# HallSensor.net
KiCad netlist of a schematic drawn in EAGLE
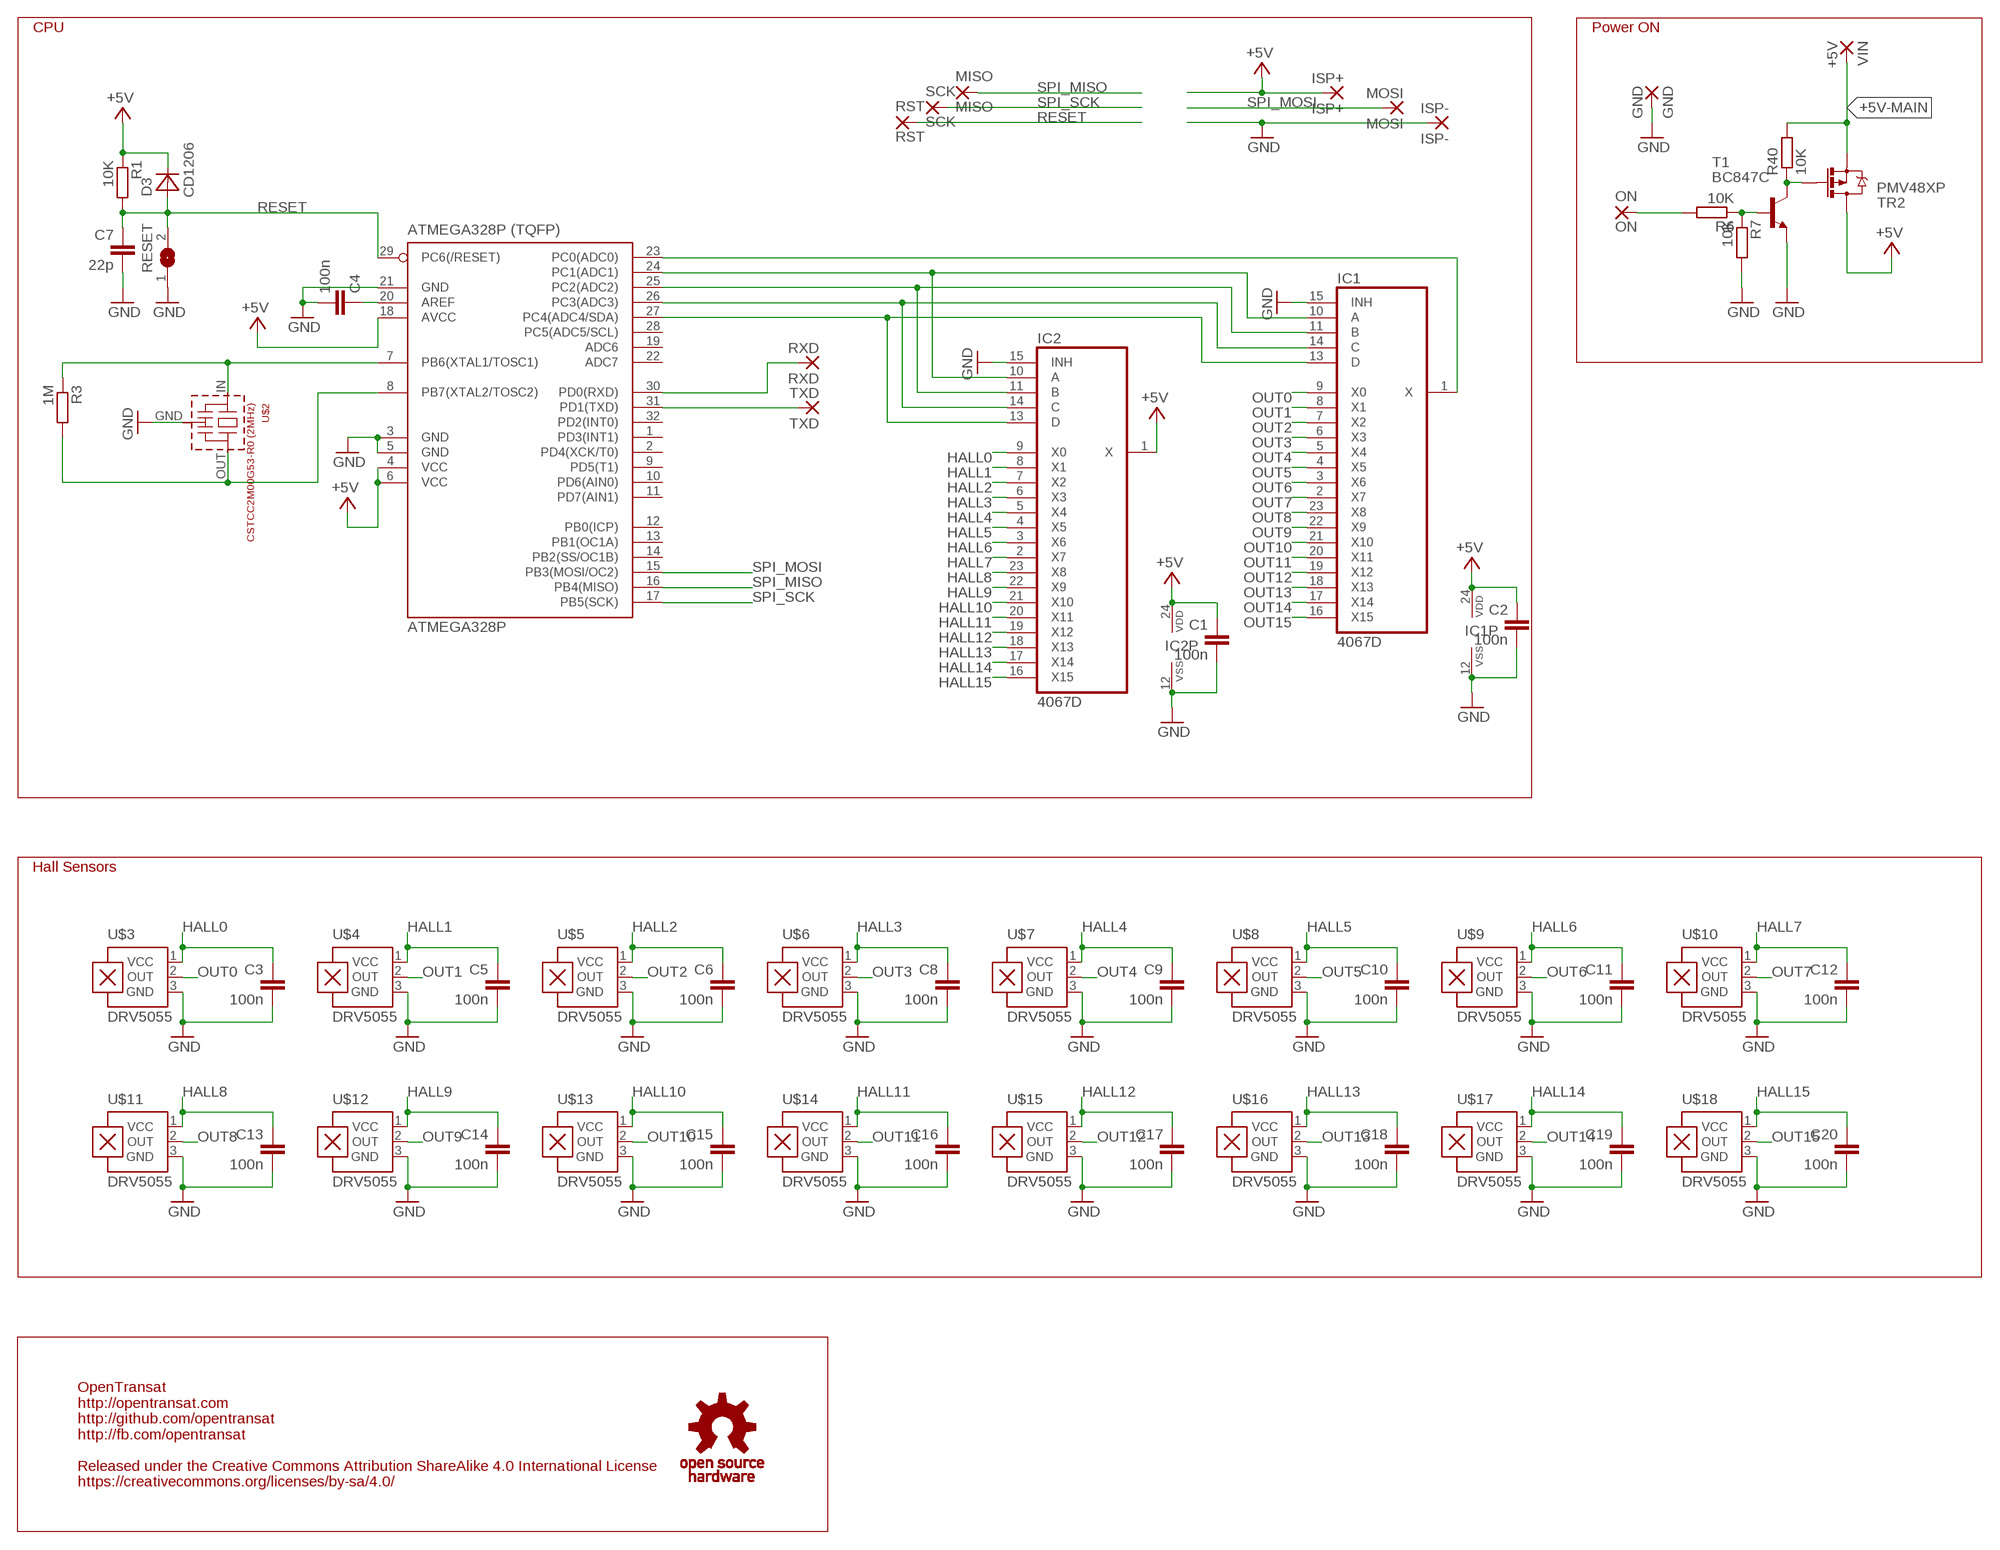
[diagram p0: schematic, sheet 1]

(export (version "E")
  (design (tool "Eeschema 10.0.6"))
  (components
    (comp (ref "ATMEGA328P")
      (value "ATMEGA328P (TQFP)")
      (footprint "eagle-import:TQFP32-08")
      (fields (field (name "MPN") "ATMEGA8-16AU"))
      (libsource (lib "eagle-import") (part "MEGA8-AI"))
    )
    (comp (ref "C1")
      (value "100n")
      (footprint "eagle-import:C0603")
      (libsource (lib "eagle-import") (part "C-EUC0603"))
    )
    (comp (ref "C2")
      (value "100n")
      (footprint "eagle-import:C0603")
      (libsource (lib "eagle-import") (part "C-EUC0603"))
    )
    (comp (ref "C3")
      (value "100n")
      (footprint "eagle-import:C0603")
      (libsource (lib "eagle-import") (part "C-EUC0603"))
    )
    (comp (ref "C4")
      (value "100n")
      (footprint "eagle-import:C0603")
      (libsource (lib "eagle-import") (part "C-EUC0603"))
    )
    (comp (ref "C5")
      (value "100n")
      (footprint "eagle-import:C0603")
      (libsource (lib "eagle-import") (part "C-EUC0603"))
    )
    (comp (ref "C6")
      (value "100n")
      (footprint "eagle-import:C0603")
      (libsource (lib "eagle-import") (part "C-EUC0603"))
    )
    (comp (ref "C7")
      (value "22p")
      (footprint "eagle-import:C0603")
      (libsource (lib "eagle-import") (part "C-EUC0603"))
    )
    (comp (ref "C8")
      (value "100n")
      (footprint "eagle-import:C0603")
      (libsource (lib "eagle-import") (part "C-EUC0603"))
    )
    (comp (ref "C9")
      (value "100n")
      (footprint "eagle-import:C0603")
      (libsource (lib "eagle-import") (part "C-EUC0603"))
    )
    (comp (ref "C10")
      (value "100n")
      (footprint "eagle-import:C0603")
      (libsource (lib "eagle-import") (part "C-EUC0603"))
    )
    (comp (ref "C11")
      (value "100n")
      (footprint "eagle-import:C0603")
      (libsource (lib "eagle-import") (part "C-EUC0603"))
    )
    (comp (ref "C12")
      (value "100n")
      (footprint "eagle-import:C0603")
      (libsource (lib "eagle-import") (part "C-EUC0603"))
    )
    (comp (ref "C13")
      (value "100n")
      (footprint "eagle-import:C0603")
      (libsource (lib "eagle-import") (part "C-EUC0603"))
    )
    (comp (ref "C14")
      (value "100n")
      (footprint "eagle-import:C0603")
      (libsource (lib "eagle-import") (part "C-EUC0603"))
    )
    (comp (ref "C15")
      (value "100n")
      (footprint "eagle-import:C0603")
      (libsource (lib "eagle-import") (part "C-EUC0603"))
    )
    (comp (ref "C16")
      (value "100n")
      (footprint "eagle-import:C0603")
      (libsource (lib "eagle-import") (part "C-EUC0603"))
    )
    (comp (ref "C17")
      (value "100n")
      (footprint "eagle-import:C0603")
      (libsource (lib "eagle-import") (part "C-EUC0603"))
    )
    (comp (ref "C18")
      (value "100n")
      (footprint "eagle-import:C0603")
      (libsource (lib "eagle-import") (part "C-EUC0603"))
    )
    (comp (ref "C19")
      (value "100n")
      (footprint "eagle-import:C0603")
      (libsource (lib "eagle-import") (part "C-EUC0603"))
    )
    (comp (ref "C20")
      (value "100n")
      (footprint "eagle-import:C0603")
      (libsource (lib "eagle-import") (part "C-EUC0603"))
    )
    (comp (ref "D3")
      (value "CD1206")
      (footprint "eagle-import:R1206")
      (libsource (lib "eagle-import") (part "CD1206"))
    )
    (comp (ref "GND")
      (value "GND")
      (footprint "eagle-import:SMD2,54-5,08")
      (libsource (lib "eagle-import") (part "SMD5"))
    )
    (comp (ref "IC1")
      (value "4067D")
      (footprint "eagle-import:SO24W")
      (libsource (lib "eagle-import") (part "4067D"))
    )
    (comp (ref "IC2")
      (value "4067D")
      (footprint "eagle-import:SO24W")
      (libsource (lib "eagle-import") (part "4067D"))
    )
    (comp (ref "ISP+")
      (value "ISP+")
      (footprint "eagle-import:SMD2,54-5,08")
      (libsource (lib "eagle-import") (part "SMD5"))
    )
    (comp (ref "ISP-")
      (value "ISP-")
      (footprint "eagle-import:SMD2,54-5,08")
      (libsource (lib "eagle-import") (part "SMD5"))
    )
    (comp (ref "MISO")
      (value "MISO")
      (footprint "eagle-import:SMD2,54-5,08")
      (libsource (lib "eagle-import") (part "SMD5"))
    )
    (comp (ref "MOSI")
      (value "MOSI")
      (footprint "eagle-import:SMD2,54-5,08")
      (libsource (lib "eagle-import") (part "SMD5"))
    )
    (comp (ref "ON")
      (value "ON")
      (footprint "eagle-import:SMD2,54-5,08")
      (libsource (lib "eagle-import") (part "SMD5"))
    )
    (comp (ref "R1")
      (value "10K")
      (footprint "eagle-import:R0603")
      (libsource (lib "eagle-import") (part "R-EU_R0603"))
    )
    (comp (ref "R3")
      (value "1M")
      (footprint "eagle-import:R0603")
      (libsource (lib "eagle-import") (part "R-EU_R0603"))
    )
    (comp (ref "R6")
      (value "10K")
      (footprint "eagle-import:R0603")
      (libsource (lib "eagle-import") (part "R-EU_R0603"))
    )
    (comp (ref "R7")
      (value "10K")
      (footprint "eagle-import:R0603")
      (libsource (lib "eagle-import") (part "R-EU_R0603"))
    )
    (comp (ref "R40")
      (value "10K")
      (footprint "eagle-import:R0603")
      (libsource (lib "eagle-import") (part "R-EU_R0603"))
    )
    (comp (ref "RESET")
      (value "SJW")
      (footprint "eagle-import:SJW")
      (libsource (lib "eagle-import") (part "SJW"))
    )
    (comp (ref "RST")
      (value "RST")
      (footprint "eagle-import:SMD2,54-5,08")
      (libsource (lib "eagle-import") (part "SMD5"))
    )
    (comp (ref "RXD")
      (value "RXD")
      (footprint "eagle-import:SMD2,54-5,08")
      (libsource (lib "eagle-import") (part "SMD5"))
    )
    (comp (ref "SCK")
      (value "SCK")
      (footprint "eagle-import:SMD2,54-5,08")
      (libsource (lib "eagle-import") (part "SMD5"))
    )
    (comp (ref "T1")
      (value "BC847C")
      (footprint "eagle-import:SOT23")
      (libsource (lib "eagle-import") (part "BC847"))
    )
    (comp (ref "TR2")
      (value "PMV48XP")
      (footprint "eagle-import:SOT23-3")
      (libsource (lib "eagle-import") (part "MOSFET-PCHANNEL_SOT23-3"))
    )
    (comp (ref "TXD")
      (value "TXD")
      (footprint "eagle-import:SMD2,54-5,08")
      (libsource (lib "eagle-import") (part "SMD5"))
    )
    (comp (ref "U$1")
      (value "OSHW_S")
      (footprint "eagle-import:OSHWS")
      (libsource (lib "eagle-import") (part "OSHW_S"))
    )
    (comp (ref "U$2")
      (value "CSTCC2M00G53-R0 (2MHz)")
      (footprint "eagle-import:CSTCC")
      (libsource (lib "eagle-import") (part "CSTCC"))
    )
    (comp (ref "U$3")
      (value "DRV5055")
      (footprint "eagle-import:SOT23")
      (libsource (lib "eagle-import") (part "DRV5055"))
    )
    (comp (ref "U$4")
      (value "DRV5055")
      (footprint "eagle-import:SOT23")
      (libsource (lib "eagle-import") (part "DRV5055"))
    )
    (comp (ref "U$5")
      (value "DRV5055")
      (footprint "eagle-import:SOT23")
      (libsource (lib "eagle-import") (part "DRV5055"))
    )
    (comp (ref "U$6")
      (value "DRV5055")
      (footprint "eagle-import:SOT23")
      (libsource (lib "eagle-import") (part "DRV5055"))
    )
    (comp (ref "U$7")
      (value "DRV5055")
      (footprint "eagle-import:SOT23")
      (libsource (lib "eagle-import") (part "DRV5055"))
    )
    (comp (ref "U$8")
      (value "DRV5055")
      (footprint "eagle-import:SOT23")
      (libsource (lib "eagle-import") (part "DRV5055"))
    )
    (comp (ref "U$9")
      (value "DRV5055")
      (footprint "eagle-import:SOT23")
      (libsource (lib "eagle-import") (part "DRV5055"))
    )
    (comp (ref "U$10")
      (value "DRV5055")
      (footprint "eagle-import:SOT23")
      (libsource (lib "eagle-import") (part "DRV5055"))
    )
    (comp (ref "U$11")
      (value "DRV5055")
      (footprint "eagle-import:SOT23")
      (libsource (lib "eagle-import") (part "DRV5055"))
    )
    (comp (ref "U$12")
      (value "DRV5055")
      (footprint "eagle-import:SOT23")
      (libsource (lib "eagle-import") (part "DRV5055"))
    )
    (comp (ref "U$13")
      (value "DRV5055")
      (footprint "eagle-import:SOT23")
      (libsource (lib "eagle-import") (part "DRV5055"))
    )
    (comp (ref "U$14")
      (value "DRV5055")
      (footprint "eagle-import:SOT23")
      (libsource (lib "eagle-import") (part "DRV5055"))
    )
    (comp (ref "U$15")
      (value "DRV5055")
      (footprint "eagle-import:SOT23")
      (libsource (lib "eagle-import") (part "DRV5055"))
    )
    (comp (ref "U$16")
      (value "DRV5055")
      (footprint "eagle-import:SOT23")
      (libsource (lib "eagle-import") (part "DRV5055"))
    )
    (comp (ref "U$17")
      (value "DRV5055")
      (footprint "eagle-import:SOT23")
      (libsource (lib "eagle-import") (part "DRV5055"))
    )
    (comp (ref "U$18")
      (value "DRV5055")
      (footprint "eagle-import:SOT23")
      (libsource (lib "eagle-import") (part "DRV5055"))
    )
    (comp (ref "VIN")
      (value "+5V")
      (footprint "eagle-import:SMD2,54-5,08")
      (libsource (lib "eagle-import") (part "SMD5"))
    )
  )
  (nets
    (net (code "1") (name "+5V") (class "Default")
      (node (ref "ATMEGA328P") (pin "18") (pinfunction "AVCC_18") (pintype "power_in"))
      (node (ref "ATMEGA328P") (pin "4") (pinfunction "VCC_4") (pintype "power_in"))
      (node (ref "ATMEGA328P") (pin "6") (pinfunction "VCC_6") (pintype "power_in"))
      (node (ref "C1") (pin "1") (pinfunction "1_1") (pintype "passive"))
      (node (ref "C2") (pin "1") (pinfunction "1_1") (pintype "passive"))
      (node (ref "D3") (pin "2") (pinfunction "C_2") (pintype "passive"))
      (node (ref "IC1") (pin "24") (pinfunction "VDD_24") (pintype "power_in"))
      (node (ref "IC2") (pin "1") (pinfunction "X_1") (pintype "output"))
      (node (ref "IC2") (pin "24") (pinfunction "VDD_24") (pintype "power_in"))
      (node (ref "ISP+") (pin "1") (pinfunction "P_1") (pintype "passive"))
      (node (ref "R1") (pin "1") (pinfunction "1_1") (pintype "passive"))
      (node (ref "TR2") (pin "3") (pinfunction "D_3") (pintype "passive"))
    )
    (net (code "2") (name "+5V-MAIN") (class "Default")
      (node (ref "R40") (pin "2") (pinfunction "2_2") (pintype "passive"))
      (node (ref "TR2") (pin "2") (pinfunction "S_2") (pintype "passive"))
      (node (ref "VIN") (pin "1") (pinfunction "P_1") (pintype "passive"))
    )
    (net (code "3") (name "/HALL0") (class "Default")
      (node (ref "C3") (pin "1") (pinfunction "1_1") (pintype "passive"))
      (node (ref "IC2") (pin "9") (pinfunction "X0_9") (pintype "input"))
      (node (ref "U$3") (pin "1") (pinfunction "VCC_1") (pintype "power_in"))
    )
    (net (code "4") (name "/HALL1") (class "Default")
      (node (ref "C5") (pin "1") (pinfunction "1_1") (pintype "passive"))
      (node (ref "IC2") (pin "8") (pinfunction "X1_8") (pintype "input"))
      (node (ref "U$4") (pin "1") (pinfunction "VCC_1") (pintype "power_in"))
    )
    (net (code "5") (name "/HALL2") (class "Default")
      (node (ref "C6") (pin "1") (pinfunction "1_1") (pintype "passive"))
      (node (ref "IC2") (pin "7") (pinfunction "X2_7") (pintype "input"))
      (node (ref "U$5") (pin "1") (pinfunction "VCC_1") (pintype "power_in"))
    )
    (net (code "6") (name "/HALL3") (class "Default")
      (node (ref "C8") (pin "1") (pinfunction "1_1") (pintype "passive"))
      (node (ref "IC2") (pin "6") (pinfunction "X3_6") (pintype "input"))
      (node (ref "U$6") (pin "1") (pinfunction "VCC_1") (pintype "power_in"))
    )
    (net (code "7") (name "/HALL4") (class "Default")
      (node (ref "C9") (pin "1") (pinfunction "1_1") (pintype "passive"))
      (node (ref "IC2") (pin "5") (pinfunction "X4_5") (pintype "input"))
      (node (ref "U$7") (pin "1") (pinfunction "VCC_1") (pintype "power_in"))
    )
    (net (code "8") (name "/HALL5") (class "Default")
      (node (ref "C10") (pin "1") (pinfunction "1_1") (pintype "passive"))
      (node (ref "IC2") (pin "4") (pinfunction "X5_4") (pintype "input"))
      (node (ref "U$8") (pin "1") (pinfunction "VCC_1") (pintype "power_in"))
    )
    (net (code "9") (name "/HALL6") (class "Default")
      (node (ref "C11") (pin "1") (pinfunction "1_1") (pintype "passive"))
      (node (ref "IC2") (pin "3") (pinfunction "X6_3") (pintype "input"))
      (node (ref "U$9") (pin "1") (pinfunction "VCC_1") (pintype "power_in"))
    )
    (net (code "10") (name "/HALL7") (class "Default")
      (node (ref "C12") (pin "1") (pinfunction "1_1") (pintype "passive"))
      (node (ref "IC2") (pin "2") (pinfunction "X7_2") (pintype "input"))
      (node (ref "U$10") (pin "1") (pinfunction "VCC_1") (pintype "power_in"))
    )
    (net (code "11") (name "/HALL8") (class "Default")
      (node (ref "C13") (pin "1") (pinfunction "1_1") (pintype "passive"))
      (node (ref "IC2") (pin "23") (pinfunction "X8_23") (pintype "input"))
      (node (ref "U$11") (pin "1") (pinfunction "VCC_1") (pintype "power_in"))
    )
    (net (code "12") (name "/HALL9") (class "Default")
      (node (ref "C14") (pin "1") (pinfunction "1_1") (pintype "passive"))
      (node (ref "IC2") (pin "22") (pinfunction "X9_22") (pintype "input"))
      (node (ref "U$12") (pin "1") (pinfunction "VCC_1") (pintype "power_in"))
    )
    (net (code "13") (name "/HALL10") (class "Default")
      (node (ref "C15") (pin "1") (pinfunction "1_1") (pintype "passive"))
      (node (ref "IC2") (pin "21") (pinfunction "X10_21") (pintype "input"))
      (node (ref "U$13") (pin "1") (pinfunction "VCC_1") (pintype "power_in"))
    )
    (net (code "14") (name "/HALL11") (class "Default")
      (node (ref "C16") (pin "1") (pinfunction "1_1") (pintype "passive"))
      (node (ref "IC2") (pin "20") (pinfunction "X11_20") (pintype "input"))
      (node (ref "U$14") (pin "1") (pinfunction "VCC_1") (pintype "power_in"))
    )
    (net (code "15") (name "/HALL12") (class "Default")
      (node (ref "C17") (pin "1") (pinfunction "1_1") (pintype "passive"))
      (node (ref "IC2") (pin "19") (pinfunction "X12_19") (pintype "input"))
      (node (ref "U$15") (pin "1") (pinfunction "VCC_1") (pintype "power_in"))
    )
    (net (code "16") (name "/HALL13") (class "Default")
      (node (ref "C18") (pin "1") (pinfunction "1_1") (pintype "passive"))
      (node (ref "IC2") (pin "18") (pinfunction "X13_18") (pintype "input"))
      (node (ref "U$16") (pin "1") (pinfunction "VCC_1") (pintype "power_in"))
    )
    (net (code "17") (name "/HALL14") (class "Default")
      (node (ref "C19") (pin "1") (pinfunction "1_1") (pintype "passive"))
      (node (ref "IC2") (pin "17") (pinfunction "X14_17") (pintype "input"))
      (node (ref "U$17") (pin "1") (pinfunction "VCC_1") (pintype "power_in"))
    )
    (net (code "18") (name "/HALL15") (class "Default")
      (node (ref "C20") (pin "1") (pinfunction "1_1") (pintype "passive"))
      (node (ref "IC2") (pin "16") (pinfunction "X15_16") (pintype "input"))
      (node (ref "U$18") (pin "1") (pinfunction "VCC_1") (pintype "power_in"))
    )
    (net (code "19") (name "/OUT0") (class "Default")
      (node (ref "IC1") (pin "9") (pinfunction "X0_9") (pintype "input"))
      (node (ref "U$3") (pin "2") (pinfunction "OUT_2") (pintype "output"))
    )
    (net (code "20") (name "/OUT1") (class "Default")
      (node (ref "IC1") (pin "8") (pinfunction "X1_8") (pintype "input"))
      (node (ref "U$4") (pin "2") (pinfunction "OUT_2") (pintype "output"))
    )
    (net (code "21") (name "/OUT2") (class "Default")
      (node (ref "IC1") (pin "7") (pinfunction "X2_7") (pintype "input"))
      (node (ref "U$5") (pin "2") (pinfunction "OUT_2") (pintype "output"))
    )
    (net (code "22") (name "/OUT3") (class "Default")
      (node (ref "IC1") (pin "6") (pinfunction "X3_6") (pintype "input"))
      (node (ref "U$6") (pin "2") (pinfunction "OUT_2") (pintype "output"))
    )
    (net (code "23") (name "/OUT4") (class "Default")
      (node (ref "IC1") (pin "5") (pinfunction "X4_5") (pintype "input"))
      (node (ref "U$7") (pin "2") (pinfunction "OUT_2") (pintype "output"))
    )
    (net (code "24") (name "/OUT5") (class "Default")
      (node (ref "IC1") (pin "4") (pinfunction "X5_4") (pintype "input"))
      (node (ref "U$8") (pin "2") (pinfunction "OUT_2") (pintype "output"))
    )
    (net (code "25") (name "/OUT6") (class "Default")
      (node (ref "IC1") (pin "3") (pinfunction "X6_3") (pintype "input"))
      (node (ref "U$9") (pin "2") (pinfunction "OUT_2") (pintype "output"))
    )
    (net (code "26") (name "/OUT7") (class "Default")
      (node (ref "IC1") (pin "2") (pinfunction "X7_2") (pintype "input"))
      (node (ref "U$10") (pin "2") (pinfunction "OUT_2") (pintype "output"))
    )
    (net (code "27") (name "/OUT8") (class "Default")
      (node (ref "IC1") (pin "23") (pinfunction "X8_23") (pintype "input"))
      (node (ref "U$11") (pin "2") (pinfunction "OUT_2") (pintype "output"))
    )
    (net (code "28") (name "/OUT9") (class "Default")
      (node (ref "IC1") (pin "22") (pinfunction "X9_22") (pintype "input"))
      (node (ref "U$12") (pin "2") (pinfunction "OUT_2") (pintype "output"))
    )
    (net (code "29") (name "/OUT10") (class "Default")
      (node (ref "IC1") (pin "21") (pinfunction "X10_21") (pintype "input"))
      (node (ref "U$13") (pin "2") (pinfunction "OUT_2") (pintype "output"))
    )
    (net (code "30") (name "/OUT11") (class "Default")
      (node (ref "IC1") (pin "20") (pinfunction "X11_20") (pintype "input"))
      (node (ref "U$14") (pin "2") (pinfunction "OUT_2") (pintype "output"))
    )
    (net (code "31") (name "/OUT12") (class "Default")
      (node (ref "IC1") (pin "19") (pinfunction "X12_19") (pintype "input"))
      (node (ref "U$15") (pin "2") (pinfunction "OUT_2") (pintype "output"))
    )
    (net (code "32") (name "/OUT13") (class "Default")
      (node (ref "IC1") (pin "18") (pinfunction "X13_18") (pintype "input"))
      (node (ref "U$16") (pin "2") (pinfunction "OUT_2") (pintype "output"))
    )
    (net (code "33") (name "/OUT14") (class "Default")
      (node (ref "IC1") (pin "17") (pinfunction "X14_17") (pintype "input"))
      (node (ref "U$17") (pin "2") (pinfunction "OUT_2") (pintype "output"))
    )
    (net (code "34") (name "/OUT15") (class "Default")
      (node (ref "IC1") (pin "16") (pinfunction "X15_16") (pintype "input"))
      (node (ref "U$18") (pin "2") (pinfunction "OUT_2") (pintype "output"))
    )
    (net (code "35") (name "/RESET") (class "Default")
      (node (ref "ATMEGA328P") (pin "29") (pinfunction "PC6(/RESET)_29") (pintype "bidirectional"))
      (node (ref "C7") (pin "1") (pinfunction "1_1") (pintype "passive"))
      (node (ref "D3") (pin "1") (pinfunction "A_1") (pintype "passive"))
      (node (ref "R1") (pin "2") (pinfunction "2_2") (pintype "passive"))
      (node (ref "RESET") (pin "2") (pinfunction "2_2") (pintype "passive"))
      (node (ref "RST") (pin "1") (pinfunction "P_1") (pintype "passive"))
    )
    (net (code "36") (name "/SPI_MISO") (class "Default")
      (node (ref "ATMEGA328P") (pin "16") (pinfunction "PB4(MISO)_16") (pintype "bidirectional"))
      (node (ref "MISO") (pin "1") (pinfunction "P_1") (pintype "passive"))
    )
    (net (code "37") (name "/SPI_MOSI") (class "Default")
      (node (ref "ATMEGA328P") (pin "15") (pinfunction "PB3(MOSI/OC2)_15") (pintype "bidirectional"))
      (node (ref "MOSI") (pin "1") (pinfunction "P_1") (pintype "passive"))
    )
    (net (code "38") (name "/SPI_SCK") (class "Default")
      (node (ref "ATMEGA328P") (pin "17") (pinfunction "PB5(SCK)_17") (pintype "bidirectional"))
      (node (ref "SCK") (pin "1") (pinfunction "P_1") (pintype "passive"))
    )
    (net (code "39") (name "GND") (class "Default")
      (node (ref "ATMEGA328P") (pin "21") (pinfunction "GND_21") (pintype "power_in"))
      (node (ref "ATMEGA328P") (pin "3") (pinfunction "GND_3") (pintype "power_in"))
      (node (ref "ATMEGA328P") (pin "5") (pinfunction "GND_5") (pintype "power_in"))
      (node (ref "C1") (pin "2") (pinfunction "2_2") (pintype "passive"))
      (node (ref "C10") (pin "2") (pinfunction "2_2") (pintype "passive"))
      (node (ref "C11") (pin "2") (pinfunction "2_2") (pintype "passive"))
      (node (ref "C12") (pin "2") (pinfunction "2_2") (pintype "passive"))
      (node (ref "C13") (pin "2") (pinfunction "2_2") (pintype "passive"))
      (node (ref "C14") (pin "2") (pinfunction "2_2") (pintype "passive"))
      (node (ref "C15") (pin "2") (pinfunction "2_2") (pintype "passive"))
      (node (ref "C16") (pin "2") (pinfunction "2_2") (pintype "passive"))
      (node (ref "C17") (pin "2") (pinfunction "2_2") (pintype "passive"))
      (node (ref "C18") (pin "2") (pinfunction "2_2") (pintype "passive"))
      (node (ref "C19") (pin "2") (pinfunction "2_2") (pintype "passive"))
      (node (ref "C2") (pin "2") (pinfunction "2_2") (pintype "passive"))
      (node (ref "C20") (pin "2") (pinfunction "2_2") (pintype "passive"))
      (node (ref "C3") (pin "2") (pinfunction "2_2") (pintype "passive"))
      (node (ref "C4") (pin "2") (pinfunction "2_2") (pintype "passive"))
      (node (ref "C5") (pin "2") (pinfunction "2_2") (pintype "passive"))
      (node (ref "C6") (pin "2") (pinfunction "2_2") (pintype "passive"))
      (node (ref "C7") (pin "2") (pinfunction "2_2") (pintype "passive"))
      (node (ref "C8") (pin "2") (pinfunction "2_2") (pintype "passive"))
      (node (ref "C9") (pin "2") (pinfunction "2_2") (pintype "passive"))
      (node (ref "GND") (pin "1") (pinfunction "P_1") (pintype "passive"))
      (node (ref "IC1") (pin "12") (pinfunction "VSS_12") (pintype "power_in"))
      (node (ref "IC1") (pin "15") (pinfunction "INH_15") (pintype "input"))
      (node (ref "IC2") (pin "12") (pinfunction "VSS_12") (pintype "power_in"))
      (node (ref "IC2") (pin "15") (pinfunction "INH_15") (pintype "input"))
      (node (ref "ISP-") (pin "1") (pinfunction "P_1") (pintype "passive"))
      (node (ref "R7") (pin "2") (pinfunction "2_2") (pintype "passive"))
      (node (ref "RESET") (pin "1") (pinfunction "1_1") (pintype "passive"))
      (node (ref "T1") (pin "2") (pinfunction "E_2") (pintype "passive"))
      (node (ref "U$10") (pin "3") (pinfunction "GND_3") (pintype "power_in"))
      (node (ref "U$11") (pin "3") (pinfunction "GND_3") (pintype "power_in"))
      (node (ref "U$12") (pin "3") (pinfunction "GND_3") (pintype "power_in"))
      (node (ref "U$13") (pin "3") (pinfunction "GND_3") (pintype "power_in"))
      (node (ref "U$14") (pin "3") (pinfunction "GND_3") (pintype "power_in"))
      (node (ref "U$15") (pin "3") (pinfunction "GND_3") (pintype "power_in"))
      (node (ref "U$16") (pin "3") (pinfunction "GND_3") (pintype "power_in"))
      (node (ref "U$17") (pin "3") (pinfunction "GND_3") (pintype "power_in"))
      (node (ref "U$18") (pin "3") (pinfunction "GND_3") (pintype "power_in"))
      (node (ref "U$2") (pin "GND") (pinfunction "GND_GND") (pintype "power_in"))
      (node (ref "U$3") (pin "3") (pinfunction "GND_3") (pintype "power_in"))
      (node (ref "U$4") (pin "3") (pinfunction "GND_3") (pintype "power_in"))
      (node (ref "U$5") (pin "3") (pinfunction "GND_3") (pintype "power_in"))
      (node (ref "U$6") (pin "3") (pinfunction "GND_3") (pintype "power_in"))
      (node (ref "U$7") (pin "3") (pinfunction "GND_3") (pintype "power_in"))
      (node (ref "U$8") (pin "3") (pinfunction "GND_3") (pintype "power_in"))
      (node (ref "U$9") (pin "3") (pinfunction "GND_3") (pintype "power_in"))
    )
    (net (code "40") (name "Net-(ATMEGA328P-AREF)") (class "Default")
      (node (ref "ATMEGA328P") (pin "20") (pinfunction "AREF_20") (pintype "passive"))
      (node (ref "C4") (pin "1") (pinfunction "1_1") (pintype "passive"))
    )
    (net (code "41") (name "Net-(ATMEGA328P-PB6(XTAL1{slash}TOSC1))") (class "Default")
      (node (ref "ATMEGA328P") (pin "7") (pinfunction "PB6(XTAL1/TOSC1)_7") (pintype "bidirectional"))
      (node (ref "R3") (pin "1") (pinfunction "1_1") (pintype "passive"))
      (node (ref "U$2") (pin "IN") (pinfunction "IN_IN") (pintype "input"))
    )
    (net (code "42") (name "Net-(ATMEGA328P-PB7(XTAL2{slash}TOSC2))") (class "Default")
      (node (ref "ATMEGA328P") (pin "8") (pinfunction "PB7(XTAL2/TOSC2)_8") (pintype "bidirectional"))
      (node (ref "R3") (pin "2") (pinfunction "2_2") (pintype "passive"))
      (node (ref "U$2") (pin "OUT") (pinfunction "OUT_OUT") (pintype "output"))
    )
    (net (code "43") (name "Net-(ATMEGA328P-PC0(ADC0))") (class "Default")
      (node (ref "ATMEGA328P") (pin "23") (pinfunction "PC0(ADC0)_23") (pintype "bidirectional"))
      (node (ref "IC1") (pin "1") (pinfunction "X_1") (pintype "output"))
    )
    (net (code "44") (name "Net-(ATMEGA328P-PC1(ADC1))") (class "Default")
      (node (ref "ATMEGA328P") (pin "24") (pinfunction "PC1(ADC1)_24") (pintype "bidirectional"))
      (node (ref "IC1") (pin "10") (pinfunction "A_10") (pintype "input"))
      (node (ref "IC2") (pin "10") (pinfunction "A_10") (pintype "input"))
    )
    (net (code "45") (name "Net-(ATMEGA328P-PC2(ADC2))") (class "Default")
      (node (ref "ATMEGA328P") (pin "25") (pinfunction "PC2(ADC2)_25") (pintype "bidirectional"))
      (node (ref "IC1") (pin "11") (pinfunction "B_11") (pintype "input"))
      (node (ref "IC2") (pin "11") (pinfunction "B_11") (pintype "input"))
    )
    (net (code "46") (name "Net-(ATMEGA328P-PC3(ADC3))") (class "Default")
      (node (ref "ATMEGA328P") (pin "26") (pinfunction "PC3(ADC3)_26") (pintype "bidirectional"))
      (node (ref "IC1") (pin "14") (pinfunction "C_14") (pintype "input"))
      (node (ref "IC2") (pin "14") (pinfunction "C_14") (pintype "input"))
    )
    (net (code "47") (name "Net-(ATMEGA328P-PC4(ADC4{slash}SDA))") (class "Default")
      (node (ref "ATMEGA328P") (pin "27") (pinfunction "PC4(ADC4/SDA)_27") (pintype "bidirectional"))
      (node (ref "IC1") (pin "13") (pinfunction "D_13") (pintype "input"))
      (node (ref "IC2") (pin "13") (pinfunction "D_13") (pintype "input"))
    )
    (net (code "48") (name "Net-(ATMEGA328P-PD0(RXD))") (class "Default")
      (node (ref "ATMEGA328P") (pin "30") (pinfunction "PD0(RXD)_30") (pintype "bidirectional"))
      (node (ref "RXD") (pin "1") (pinfunction "P_1") (pintype "passive"))
    )
    (net (code "49") (name "Net-(ATMEGA328P-PD1(TXD))") (class "Default")
      (node (ref "ATMEGA328P") (pin "31") (pinfunction "PD1(TXD)_31") (pintype "bidirectional"))
      (node (ref "TXD") (pin "1") (pinfunction "P_1") (pintype "passive"))
    )
    (net (code "50") (name "Net-(ON-P)") (class "Default")
      (node (ref "ON") (pin "1") (pinfunction "P_1") (pintype "passive"))
      (node (ref "R6") (pin "2") (pinfunction "2_2") (pintype "passive"))
    )
    (net (code "51") (name "Net-(T1-B)") (class "Default")
      (node (ref "R6") (pin "1") (pinfunction "1_1") (pintype "passive"))
      (node (ref "R7") (pin "1") (pinfunction "1_1") (pintype "passive"))
      (node (ref "T1") (pin "1") (pinfunction "B_1") (pintype "passive"))
    )
    (net (code "52") (name "Net-(T1-C)") (class "Default")
      (node (ref "R40") (pin "1") (pinfunction "1_1") (pintype "passive"))
      (node (ref "T1") (pin "3") (pinfunction "C_3") (pintype "passive"))
      (node (ref "TR2") (pin "1") (pinfunction "G_1") (pintype "passive"))
    )
    (net (code "53") (name "unconnected-(ATMEGA328P-ADC6-Pad19)") (class "Default")
      (node (ref "ATMEGA328P") (pin "19") (pinfunction "ADC6_19") (pintype "bidirectional"))
    )
    (net (code "54") (name "unconnected-(ATMEGA328P-ADC7-Pad22)") (class "Default")
      (node (ref "ATMEGA328P") (pin "22") (pinfunction "ADC7_22") (pintype "bidirectional"))
    )
    (net (code "55") (name "unconnected-(ATMEGA328P-PB0(ICP)-Pad12)") (class "Default")
      (node (ref "ATMEGA328P") (pin "12") (pinfunction "PB0(ICP)_12") (pintype "bidirectional"))
    )
    (net (code "56") (name "unconnected-(ATMEGA328P-PB1(OC1A)-Pad13)") (class "Default")
      (node (ref "ATMEGA328P") (pin "13") (pinfunction "PB1(OC1A)_13") (pintype "bidirectional"))
    )
    (net (code "57") (name "unconnected-(ATMEGA328P-PB2(SS{slash}OC1B)-Pad14)") (class "Default")
      (node (ref "ATMEGA328P") (pin "14") (pinfunction "PB2(SS/OC1B)_14") (pintype "bidirectional"))
    )
    (net (code "58") (name "unconnected-(ATMEGA328P-PC5(ADC5{slash}SCL)-Pad28)") (class "Default")
      (node (ref "ATMEGA328P") (pin "28") (pinfunction "PC5(ADC5/SCL)_28") (pintype "bidirectional"))
    )
    (net (code "59") (name "unconnected-(ATMEGA328P-PD2(INT0)-Pad32)") (class "Default")
      (node (ref "ATMEGA328P") (pin "32") (pinfunction "PD2(INT0)_32") (pintype "bidirectional"))
    )
    (net (code "60") (name "unconnected-(ATMEGA328P-PD3(INT1)-Pad1)") (class "Default")
      (node (ref "ATMEGA328P") (pin "1") (pinfunction "PD3(INT1)_1") (pintype "bidirectional"))
    )
    (net (code "61") (name "unconnected-(ATMEGA328P-PD4(XCK{slash}T0)-Pad2)") (class "Default")
      (node (ref "ATMEGA328P") (pin "2") (pinfunction "PD4(XCK/T0)_2") (pintype "bidirectional"))
    )
    (net (code "62") (name "unconnected-(ATMEGA328P-PD5(T1)-Pad9)") (class "Default")
      (node (ref "ATMEGA328P") (pin "9") (pinfunction "PD5(T1)_9") (pintype "bidirectional"))
    )
    (net (code "63") (name "unconnected-(ATMEGA328P-PD6(AIN0)-Pad10)") (class "Default")
      (node (ref "ATMEGA328P") (pin "10") (pinfunction "PD6(AIN0)_10") (pintype "bidirectional"))
    )
    (net (code "64") (name "unconnected-(ATMEGA328P-PD7(AIN1)-Pad11)") (class "Default")
      (node (ref "ATMEGA328P") (pin "11") (pinfunction "PD7(AIN1)_11") (pintype "bidirectional"))
    )
  )
)
